# attinier85-motherboard-smd-mk-2_1.net
KiCad netlist of a schematic drawn in EAGLE
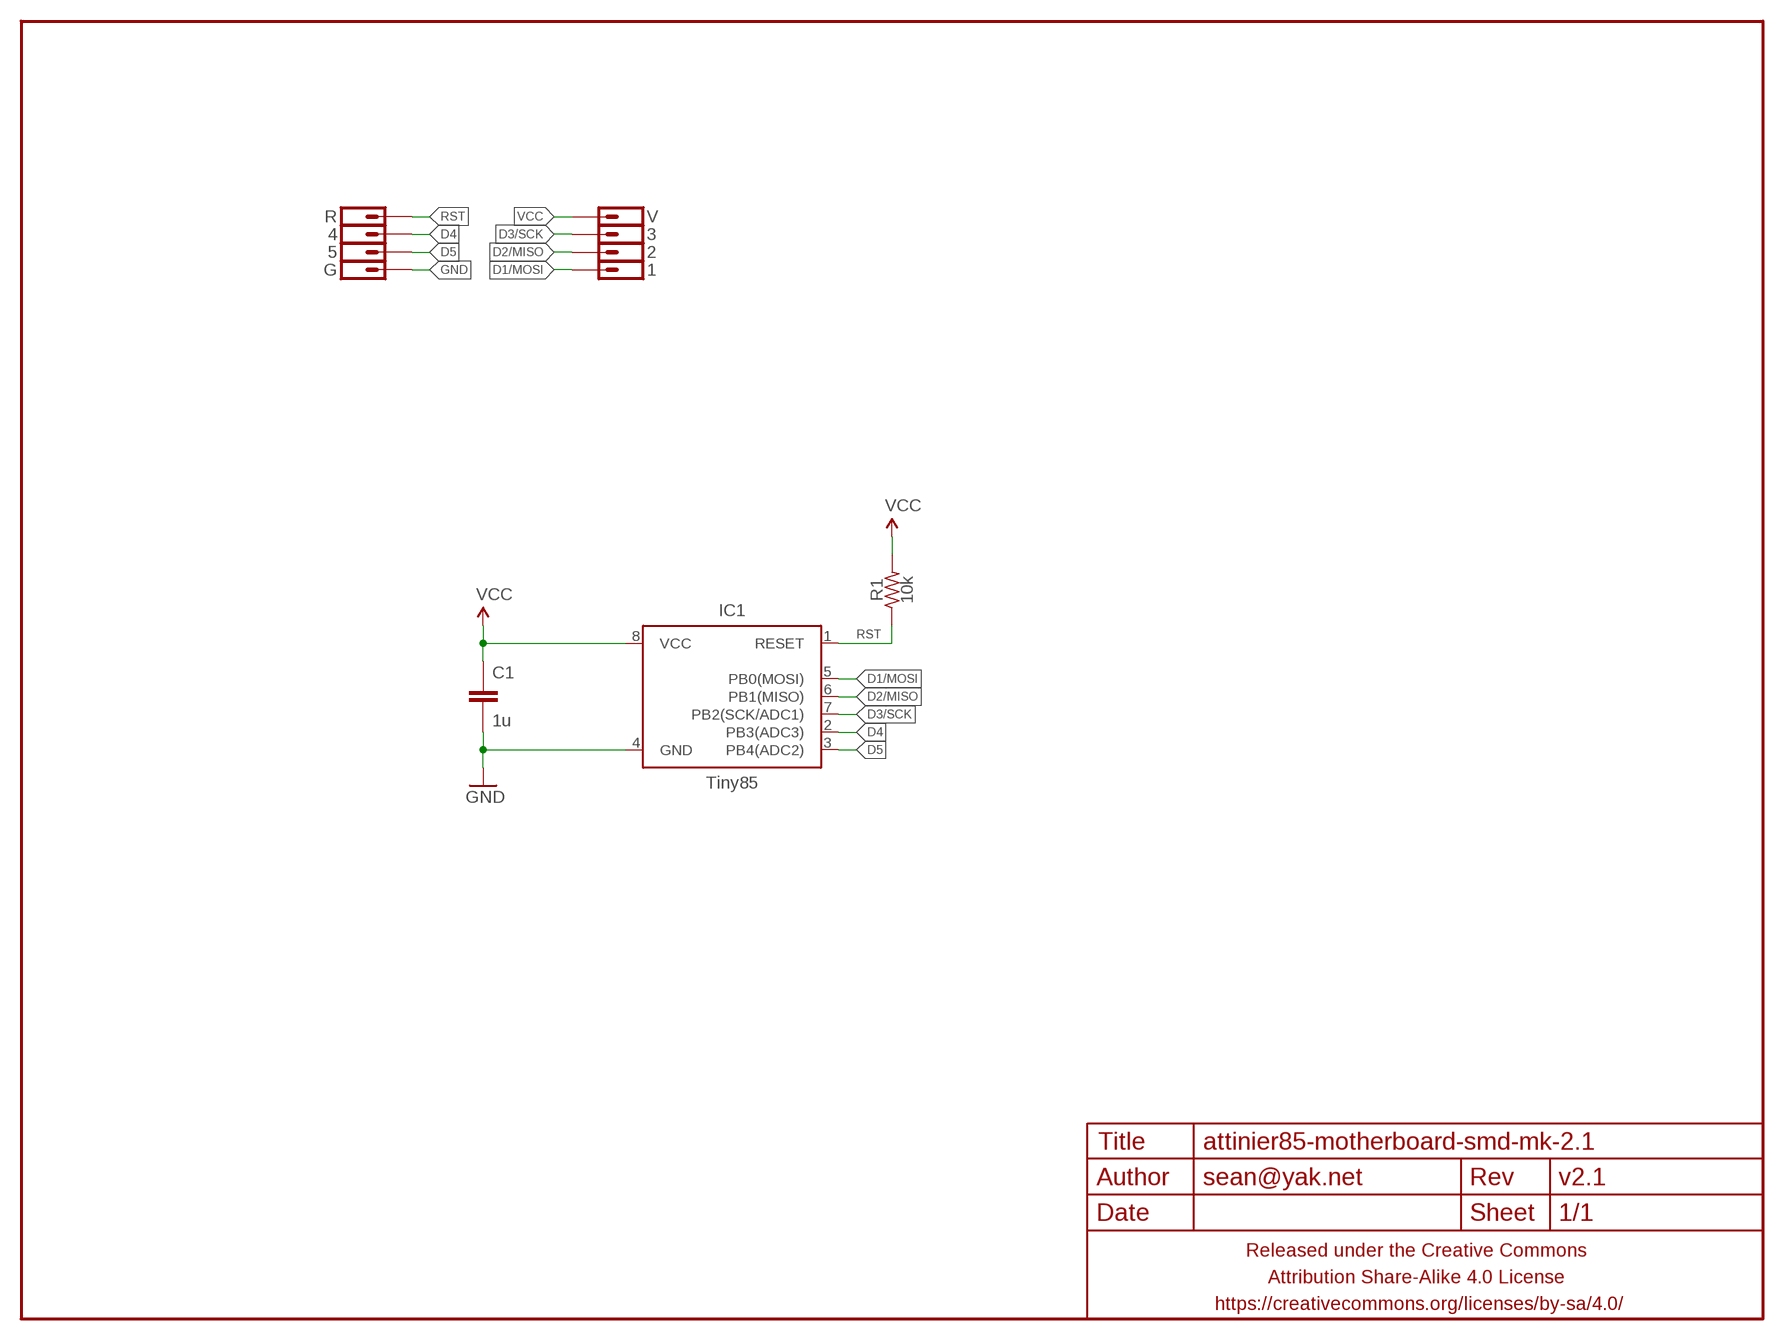
[diagram p0: schematic, sheet 1]

(export (version "E")
  (design (tool "Eeschema 10.0.6"))
  (components
    (comp (ref "1")
      (value "M01PTH-0.9MM")
      (footprint "eagle-import:1X01-0.9MM")
      (libsource (lib "eagle-import") (part "M01PTH-0.9MM"))
    )
    (comp (ref "2")
      (value "M01PTH-0.9MM")
      (footprint "eagle-import:1X01-0.9MM")
      (libsource (lib "eagle-import") (part "M01PTH-0.9MM"))
    )
    (comp (ref "3")
      (value "M01PTH-0.9MM")
      (footprint "eagle-import:1X01-0.9MM")
      (libsource (lib "eagle-import") (part "M01PTH-0.9MM"))
    )
    (comp (ref "4")
      (value "M01PTH-0.9MM")
      (footprint "eagle-import:1X01-0.9MM")
      (libsource (lib "eagle-import") (part "M01PTH-0.9MM"))
    )
    (comp (ref "5")
      (value "M01PTH-0.9MM")
      (footprint "eagle-import:1X01-0.9MM")
      (libsource (lib "eagle-import") (part "M01PTH-0.9MM"))
    )
    (comp (ref "C1")
      (value "1u")
      (footprint "eagle-import:C0603-TIGHTER")
      (libsource (lib "eagle-import") (part "CAPACITOR-CERAMICC0603-TIGHTER"))
    )
    (comp (ref "FRAME1")
      (value "FRAME-LETTERNO_PACKAGE")
      (footprint "eagle-import:DUMMY")
      (fields (field (name "DESIGNER") "sean@yak.net") (field (name "VERSION") "v2.1"))
      (libsource (lib "eagle-import") (part "FRAME-LETTERNO_PACKAGE"))
    )
    (comp (ref "G")
      (value "M01PTH-0.9MM")
      (footprint "eagle-import:1X01-0.9MM")
      (libsource (lib "eagle-import") (part "M01PTH-0.9MM"))
    )
    (comp (ref "IC1")
      (value "Tiny85")
      (footprint "eagle-import:SO08-EIAJ")
      (libsource (lib "eagle-import") (part "ATTINY45TINY85-20-SOICW"))
    )
    (comp (ref "R")
      (value "M01PTH-0.9MM")
      (footprint "eagle-import:1X01-0.9MM")
      (libsource (lib "eagle-import") (part "M01PTH-0.9MM"))
    )
    (comp (ref "R1")
      (value "10k")
      (footprint "eagle-import:R0603-TIGHTER")
      (libsource (lib "eagle-import") (part "RESISTORR0603-TIGHTER"))
    )
    (comp (ref "V")
      (value "M01PTH-0.9MM")
      (footprint "eagle-import:1X01-0.9MM")
      (libsource (lib "eagle-import") (part "M01PTH-0.9MM"))
    )
  )
  (nets
    (net (code "1") (name "D1{slash}MOSI") (class "Default")
      (node (ref "1") (pin "1") (pinfunction "1_1") (pintype "passive"))
      (node (ref "IC1") (pin "5") (pinfunction "PB0(MOSI)_5") (pintype "bidirectional"))
    )
    (net (code "2") (name "D2{slash}MISO") (class "Default")
      (node (ref "2") (pin "1") (pinfunction "1_1") (pintype "passive"))
      (node (ref "IC1") (pin "6") (pinfunction "PB1(MISO)_6") (pintype "bidirectional"))
    )
    (net (code "3") (name "D3{slash}SCK") (class "Default")
      (node (ref "3") (pin "1") (pinfunction "1_1") (pintype "passive"))
      (node (ref "IC1") (pin "7") (pinfunction "PB2(SCK/ADC1)_7") (pintype "bidirectional"))
    )
    (net (code "4") (name "D4") (class "Default")
      (node (ref "4") (pin "1") (pinfunction "1_1") (pintype "passive"))
      (node (ref "IC1") (pin "2") (pinfunction "PB3(ADC3)_2") (pintype "bidirectional"))
    )
    (net (code "5") (name "D5") (class "Default")
      (node (ref "5") (pin "1") (pinfunction "1_1") (pintype "passive"))
      (node (ref "IC1") (pin "3") (pinfunction "PB4(ADC2)_3") (pintype "bidirectional"))
    )
    (net (code "6") (name "GND") (class "Default")
      (node (ref "C1") (pin "2") (pinfunction "2_2") (pintype "passive"))
      (node (ref "G") (pin "1") (pinfunction "1_1") (pintype "passive"))
      (node (ref "IC1") (pin "4") (pinfunction "GND_4") (pintype "bidirectional"))
    )
    (net (code "7") (name "RST") (class "Default")
      (node (ref "IC1") (pin "1") (pinfunction "RESET_1") (pintype "bidirectional"))
      (node (ref "R") (pin "1") (pinfunction "1_1") (pintype "passive"))
      (node (ref "R1") (pin "1") (pinfunction "1_1") (pintype "passive"))
    )
    (net (code "8") (name "VCC") (class "Default")
      (node (ref "C1") (pin "1") (pinfunction "1_1") (pintype "passive"))
      (node (ref "IC1") (pin "8") (pinfunction "VCC_8") (pintype "bidirectional"))
      (node (ref "R1") (pin "2") (pinfunction "2_2") (pintype "passive"))
      (node (ref "V") (pin "1") (pinfunction "1_1") (pintype "passive"))
    )
  )
)
